# CH32V005D6U.net
KiCad netlist of a schematic drawn in Altium Designer
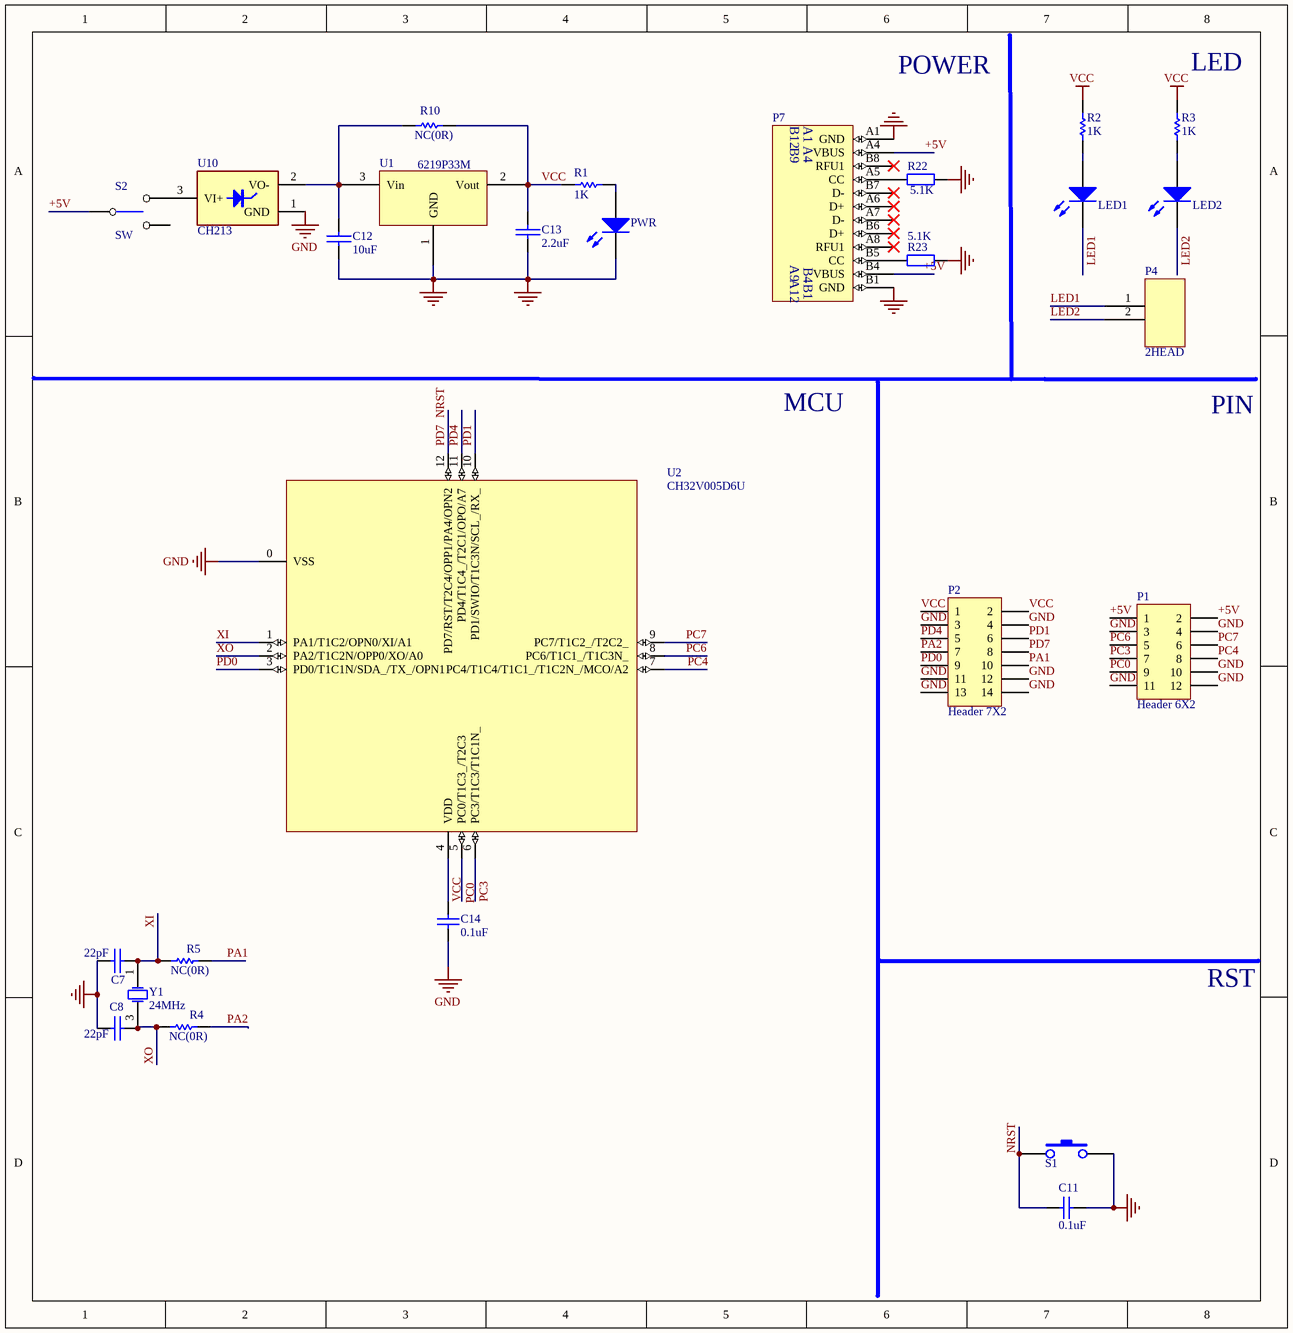
[diagram p0: CH32V005D6U.SchDoc]

(export (version "E")
  (design (tool "Eeschema 10.0.6"))
  (components
    (comp (ref "C7")
      (value "22pF")
      (footprint "0402_C")
      (description "Capacitor")
      (libsource (lib "*") (part "CAP"))
    )
    (comp (ref "C8")
      (value "22pF")
      (footprint "0402_C")
      (description "Capacitor")
      (libsource (lib "*") (part "CAP"))
    )
    (comp (ref "C11")
      (value "0.1uF")
      (footprint "0603_C")
      (description "Capacitor")
      (fields (field (name "PUBLISHER") "Altium Limited"))
      (libsource (lib "*") (part "Cap"))
    )
    (comp (ref "C12")
      (value "10uF")
      (footprint "0603_C")
      (description "Capacitor")
      (libsource (lib "wch_sch_others") (part "CAP"))
    )
    (comp (ref "C13")
      (value "2.2uF")
      (footprint "0402_C")
      (description "Capacitor")
      (libsource (lib "wch_sch_others") (part "CAP"))
    )
    (comp (ref "C14")
      (value "0.1uF")
      (footprint "0603_C")
      (description "Capacitor")
      (fields (field (name "PUBLISHER") "Altium Limited"))
      (libsource (lib "*") (part "Cap"))
    )
    (comp (ref "LED1")
      (value "LED1   blue")
      (footprint "0603+")
      (description "Typical INFRARED GaAs LED")
      (fields (field (name "PUBLISHER") "Altium Limited"))
      (libsource (lib "") (part "LED0_1"))
    )
    (comp (ref "LED2")
      (value "LED2  blue")
      (footprint "0603+")
      (description "Typical INFRARED GaAs LED")
      (fields (field (name "PUBLISHER") "Altium Limited"))
      (libsource (lib "") (part "LED0_1"))
    )
    (comp (ref "P1")
      (value "Header 6X2")
      (footprint "HDR2X6")
      (description "Header, 6-Pin, Dual row")
      (fields (field (name "PUBLISHER") "Altium Limited"))
      (libsource (lib "Miscellaneous Connectors") (part "Header 6X2"))
    )
    (comp (ref "P2")
      (value "Header 7X2")
      (footprint "HDR2X7")
      (description "Header, 7-Pin, Dual row")
      (fields (field (name "PUBLISHER") "Altium Limited"))
      (libsource (lib "Miscellaneous Connectors") (part "Header 7X2"))
    )
    (comp (ref "P4") (value "2HEAD") (footprint "SIP2-2.54mm") (libsource (lib "*") (part "2HEAD")))
    (comp (ref "P7")
      (value "TYPE-C")
      (footprint "TYPE-C-Receptacle-2.0")
      (libsource (lib "*") (part "TYPE-C1"))
    )
    (comp (ref "PWR")
      (value "POWER  red")
      (footprint "0603+")
      (description "Typical INFRARED GaAs LED")
      (fields (field (name "PUBLISHER") "Altium Limited"))
      (libsource (lib "*") (part "LED0"))
    )
    (comp (ref "R1")
      (value "1K")
      (footprint "0402")
      (description "Semiconductor Resistor")
      (fields (field (name "PUBLISHER") "Altium Limited"))
      (libsource (lib "*") (part "Res Semi"))
    )
    (comp (ref "R2")
      (value "1K")
      (footprint "0402")
      (description "Semiconductor Resistor")
      (fields (field (name "PUBLISHER") "Altium Limited"))
      (libsource (lib "*") (part "Res Semi"))
    )
    (comp (ref "R3")
      (value "1K")
      (footprint "0402")
      (description "Semiconductor Resistor")
      (fields (field (name "PUBLISHER") "Altium Limited"))
      (libsource (lib "*") (part "Res Semi"))
    )
    (comp (ref "R4")
      (value "NC(0R)")
      (footprint "0402")
      (description "Semiconductor Resistor")
      (fields (field (name "Comment") "0R") (field (name "PUBLISHER") "Altium Limited"))
      (libsource (lib "*") (part "Res Semi"))
    )
    (comp (ref "R5")
      (value "NC(0R)")
      (footprint "0402")
      (description "Semiconductor Resistor")
      (fields (field (name "Comment") "0R") (field (name "PUBLISHER") "Altium Limited"))
      (libsource (lib "*") (part "Res Semi"))
    )
    (comp (ref "R10")
      (value "NC(0R)")
      (footprint "0402")
      (description "Semiconductor Resistor")
      (fields (field (name "Comment") "0R") (field (name "PUBLISHER") "Altium Limited"))
      (libsource (lib "*") (part "Res Semi"))
    )
    (comp (ref "R22")
      (value "5.1K")
      (footprint "0402")
      (description "Resistor")
      (libsource (lib "Miscellaneous Devices") (part "Res2"))
    )
    (comp (ref "R23")
      (value "5.1K")
      (footprint "0402")
      (description "Resistor")
      (libsource (lib "Miscellaneous Devices") (part "Res2"))
    )
    (comp (ref "S1") (value "NRST") (footprint "SMD_6.1x3.65x2.5mm-KEY") (libsource (lib "*") (part "KEY")))
    (comp (ref "S2") (value "SW") (footprint "SW1") (libsource (lib "*") (part "SW")))
    (comp (ref "U1")
      (value "6219P33M")
      (footprint "SOT-23")
      (libsource (lib "wch_sch_others") (part "6219P33M"))
    )
    (comp (ref "U2")
      (value "CH32V005D6U")
      (footprint "QFN12_2X2")
      (description "RISC-V MCU, 48MHz, ADC/OPA/2*UART/I2C")
      (libsource (lib "DHXXXSCH") (part "CH32V005D6U6"))
    )
    (comp (ref "U10")
      (value "CH213")
      (footprint "SOT-23-3")
      (description "Ideal Diode 5V*1A")
      (libsource (lib "CHXXX") (part "CH213E"))
    )
    (comp (ref "Y1")
      (value "24MHz")
      (footprint "XT3225")
      (description "Crystal Oscillator")
      (fields (field (name "PUBLISHER") "Altium Limited"))
      (libsource (lib "*") (part "XTAL"))
    )
  )
  (nets
    (net (code "1") (name "/+5V") (class "Default")
      (node (ref "P1") (pin "1") (pinfunction "1_1") (pintype "passive"))
      (node (ref "P1") (pin "2") (pinfunction "2_2") (pintype "passive"))
      (node (ref "P7") (pin "A4") (pinfunction "VBUS_A4") (pintype "bidirectional"))
      (node (ref "P7") (pin "B4") (pinfunction "VBUS_B4") (pintype "bidirectional"))
      (node (ref "S2") (pin "1") (pinfunction "1_1") (pintype "passive"))
    )
    (net (code "2") (name "/LED1") (class "Default")
      (node (ref "LED1") (pin "2") (pinfunction "K_2") (pintype "passive"))
      (node (ref "P4") (pin "1") (pintype "passive"))
    )
    (net (code "3") (name "/LED2") (class "Default")
      (node (ref "LED2") (pin "2") (pinfunction "K_2") (pintype "passive"))
      (node (ref "P4") (pin "2") (pintype "passive"))
    )
    (net (code "4") (name "/NRST") (class "Default")
      (node (ref "C11") (pin "2") (pinfunction "2_2") (pintype "passive"))
      (node (ref "P2") (pin "8") (pinfunction "8_8") (pintype "passive"))
      (node (ref "S1") (pin "1") (pinfunction "1_1") (pintype "passive"))
      (node (ref "U2") (pin "12") (pinfunction "PD7/RST/T2C4/OPP1/PA4/OPN2_12") (pintype "bidirectional"))
    )
    (net (code "5") (name "/PA1") (class "Default")
      (node (ref "P2") (pin "10") (pinfunction "10_10") (pintype "passive"))
      (node (ref "R5") (pin "2") (pinfunction "2_2") (pintype "passive"))
    )
    (net (code "6") (name "/PA2") (class "Default")
      (node (ref "P2") (pin "7") (pinfunction "7_7") (pintype "passive"))
      (node (ref "R4") (pin "2") (pinfunction "2_2") (pintype "passive"))
    )
    (net (code "7") (name "/PC0") (class "Default")
      (node (ref "P1") (pin "9") (pinfunction "9_9") (pintype "passive"))
      (node (ref "U2") (pin "5") (pinfunction "PC0/T1C3_/T2C3_5") (pintype "bidirectional"))
    )
    (net (code "8") (name "/PC3") (class "Default")
      (node (ref "P1") (pin "7") (pinfunction "7_7") (pintype "passive"))
      (node (ref "U2") (pin "6") (pinfunction "PC3/T1C3/T1C1N__6") (pintype "bidirectional"))
    )
    (net (code "9") (name "/PC4") (class "Default")
      (node (ref "P1") (pin "8") (pinfunction "8_8") (pintype "passive"))
      (node (ref "U2") (pin "7") (pinfunction "PC4/T1C4/T1C1_/T1C2N_/MCO/A2_7") (pintype "bidirectional"))
    )
    (net (code "10") (name "/PC6") (class "Default")
      (node (ref "P1") (pin "5") (pinfunction "5_5") (pintype "passive"))
      (node (ref "U2") (pin "8") (pinfunction "PC6/T1C1_/T1C3N__8") (pintype "bidirectional"))
    )
    (net (code "11") (name "/PC7") (class "Default")
      (node (ref "P1") (pin "6") (pinfunction "6_6") (pintype "passive"))
      (node (ref "U2") (pin "9") (pinfunction "PC7/T1C2_/T2C2__9") (pintype "bidirectional"))
    )
    (net (code "12") (name "/PD0") (class "Default")
      (node (ref "P2") (pin "9") (pinfunction "9_9") (pintype "passive"))
      (node (ref "U2") (pin "3") (pinfunction "PD0/T1C1N/SDA_/TX_/OPN1_3") (pintype "bidirectional"))
    )
    (net (code "13") (name "/PD1") (class "Default")
      (node (ref "P2") (pin "6") (pinfunction "6_6") (pintype "passive"))
      (node (ref "U2") (pin "10") (pinfunction "PD1/SWIO/T1C3N/SCL_/RX__10") (pintype "bidirectional"))
    )
    (net (code "14") (name "/PD4") (class "Default")
      (node (ref "P2") (pin "5") (pinfunction "5_5") (pintype "passive"))
      (node (ref "U2") (pin "11") (pinfunction "PD4/T1C4_/T2C1/OPO/A7_11") (pintype "bidirectional"))
    )
    (net (code "15") (name "/XI") (class "Default")
      (node (ref "C7") (pin "2") (pinfunction "2_2") (pintype "passive"))
      (node (ref "R5") (pin "1") (pinfunction "1_1") (pintype "passive"))
      (node (ref "U2") (pin "1") (pinfunction "PA1/T1C2/OPN0/XI/A1_1") (pintype "bidirectional"))
      (node (ref "Y1") (pin "1") (pinfunction "OSC1_1") (pintype "passive"))
    )
    (net (code "16") (name "/XO") (class "Default")
      (node (ref "C8") (pin "2") (pinfunction "2_2") (pintype "passive"))
      (node (ref "R4") (pin "1") (pinfunction "1_1") (pintype "passive"))
      (node (ref "U2") (pin "2") (pinfunction "PA2/T1C2N/OPP0/XO/A0_2") (pintype "bidirectional"))
      (node (ref "Y1") (pin "3") (pinfunction "OSC2_3") (pintype "passive"))
    )
    (net (code "17") (name "GND") (class "Default")
      (node (ref "C11") (pin "1") (pinfunction "1_1") (pintype "passive"))
      (node (ref "C12") (pin "2") (pinfunction "2_2") (pintype "passive"))
      (node (ref "C13") (pin "1") (pinfunction "1_1") (pintype "passive"))
      (node (ref "C14") (pin "1") (pinfunction "1_1") (pintype "passive"))
      (node (ref "C7") (pin "1") (pinfunction "1_1") (pintype "passive"))
      (node (ref "C8") (pin "1") (pinfunction "1_1") (pintype "passive"))
      (node (ref "P1") (pin "10") (pinfunction "10_10") (pintype "passive"))
      (node (ref "P1") (pin "11") (pinfunction "11_11") (pintype "passive"))
      (node (ref "P1") (pin "12") (pinfunction "12_12") (pintype "passive"))
      (node (ref "P1") (pin "3") (pinfunction "3_3") (pintype "passive"))
      (node (ref "P1") (pin "4") (pinfunction "4_4") (pintype "passive"))
      (node (ref "P2") (pin "11") (pinfunction "11_11") (pintype "passive"))
      (node (ref "P2") (pin "12") (pinfunction "12_12") (pintype "passive"))
      (node (ref "P2") (pin "13") (pinfunction "13_13") (pintype "passive"))
      (node (ref "P2") (pin "14") (pinfunction "14_14") (pintype "passive"))
      (node (ref "P2") (pin "3") (pinfunction "3_3") (pintype "passive"))
      (node (ref "P2") (pin "4") (pinfunction "4_4") (pintype "passive"))
      (node (ref "P7") (pin "A1") (pinfunction "GND_A1") (pintype "bidirectional"))
      (node (ref "P7") (pin "B1") (pinfunction "GND_B1") (pintype "bidirectional"))
      (node (ref "PWR") (pin "2") (pinfunction "K_2") (pintype "passive"))
      (node (ref "R22") (pin "2") (pinfunction "2_2") (pintype "passive"))
      (node (ref "R23") (pin "2") (pinfunction "2_2") (pintype "passive"))
      (node (ref "S1") (pin "2") (pinfunction "2_2") (pintype "passive"))
      (node (ref "U1") (pin "1") (pinfunction "GND_1") (pintype "passive"))
      (node (ref "U10") (pin "1") (pinfunction "GND_1") (pintype "power_in"))
      (node (ref "U2") (pin "0") (pinfunction "VSS_0") (pintype "power_in"))
    )
    (net (code "18") (name "Net-(LED1-A)") (class "Default")
      (node (ref "LED1") (pin "1") (pinfunction "A_1") (pintype "passive"))
      (node (ref "R2") (pin "2") (pinfunction "2_2") (pintype "passive"))
    )
    (net (code "19") (name "Net-(LED2-A)") (class "Default")
      (node (ref "LED2") (pin "1") (pinfunction "A_1") (pintype "passive"))
      (node (ref "R3") (pin "2") (pinfunction "2_2") (pintype "passive"))
    )
    (net (code "20") (name "Net-(P7-CC-PadA5)") (class "Default")
      (node (ref "P7") (pin "A5") (pinfunction "CC_A5") (pintype "bidirectional"))
      (node (ref "R22") (pin "1") (pinfunction "1_1") (pintype "passive"))
    )
    (net (code "21") (name "Net-(P7-CC-PadB5)") (class "Default")
      (node (ref "P7") (pin "B5") (pinfunction "CC_B5") (pintype "bidirectional"))
      (node (ref "R23") (pin "1") (pinfunction "1_1") (pintype "passive"))
    )
    (net (code "22") (name "Net-(PWR-A)") (class "Default")
      (node (ref "PWR") (pin "1") (pinfunction "A_1") (pintype "passive"))
      (node (ref "R1") (pin "1") (pinfunction "1_1") (pintype "passive"))
    )
    (net (code "23") (name "Net-(U1-Vin)") (class "Default")
      (node (ref "C12") (pin "1") (pinfunction "1_1") (pintype "passive"))
      (node (ref "R10") (pin "1") (pinfunction "1_1") (pintype "passive"))
      (node (ref "U1") (pin "3") (pinfunction "Vin_3") (pintype "passive"))
      (node (ref "U10") (pin "2") (pinfunction "VO-_2") (pintype "power_in"))
    )
    (net (code "24") (name "Net-(U10-VI+)") (class "Default")
      (node (ref "S2") (pin "3") (pinfunction "3_3") (pintype "passive"))
      (node (ref "U10") (pin "3") (pinfunction "VI+_3") (pintype "power_in"))
    )
    (net (code "25") (name "VCC") (class "Default")
      (node (ref "C13") (pin "2") (pinfunction "2_2") (pintype "passive"))
      (node (ref "C14") (pin "2") (pinfunction "2_2") (pintype "passive"))
      (node (ref "P2") (pin "1") (pinfunction "1_1") (pintype "passive"))
      (node (ref "P2") (pin "2") (pinfunction "2_2") (pintype "passive"))
      (node (ref "R1") (pin "2") (pinfunction "2_2") (pintype "passive"))
      (node (ref "R10") (pin "2") (pinfunction "2_2") (pintype "passive"))
      (node (ref "R2") (pin "1") (pinfunction "1_1") (pintype "passive"))
      (node (ref "R3") (pin "1") (pinfunction "1_1") (pintype "passive"))
      (node (ref "U1") (pin "2") (pinfunction "Vout_2") (pintype "passive"))
      (node (ref "U2") (pin "4") (pinfunction "VDD_4") (pintype "power_in"))
    )
    (net (code "26") (name "unconnected-(P7-D+-PadA6)") (class "Default")
      (node (ref "P7") (pin "A6") (pinfunction "D+_A6") (pintype "bidirectional+no_connect"))
    )
    (net (code "27") (name "unconnected-(P7-D+-PadB6)") (class "Default")
      (node (ref "P7") (pin "B6") (pinfunction "D+_B6") (pintype "bidirectional+no_connect"))
    )
    (net (code "28") (name "unconnected-(P7-D--PadA7)") (class "Default")
      (node (ref "P7") (pin "A7") (pinfunction "D-_A7") (pintype "bidirectional+no_connect"))
    )
    (net (code "29") (name "unconnected-(P7-D--PadB7)") (class "Default")
      (node (ref "P7") (pin "B7") (pinfunction "D-_B7") (pintype "bidirectional+no_connect"))
    )
    (net (code "30") (name "unconnected-(P7-RFU1-PadA8)") (class "Default")
      (node (ref "P7") (pin "A8") (pinfunction "RFU1_A8") (pintype "bidirectional+no_connect"))
    )
    (net (code "31") (name "unconnected-(P7-RFU1-PadB8)") (class "Default")
      (node (ref "P7") (pin "B8") (pinfunction "RFU1_B8") (pintype "bidirectional+no_connect"))
    )
    (net (code "32") (name "unconnected-(S2-Pad2)") (class "Default")
      (node (ref "S2") (pin "2") (pinfunction "2_2") (pintype "passive"))
    )
  )
)
